# AJH_ss12144_v1_03.net
KiCad netlist of a schematic drawn in EAGLE
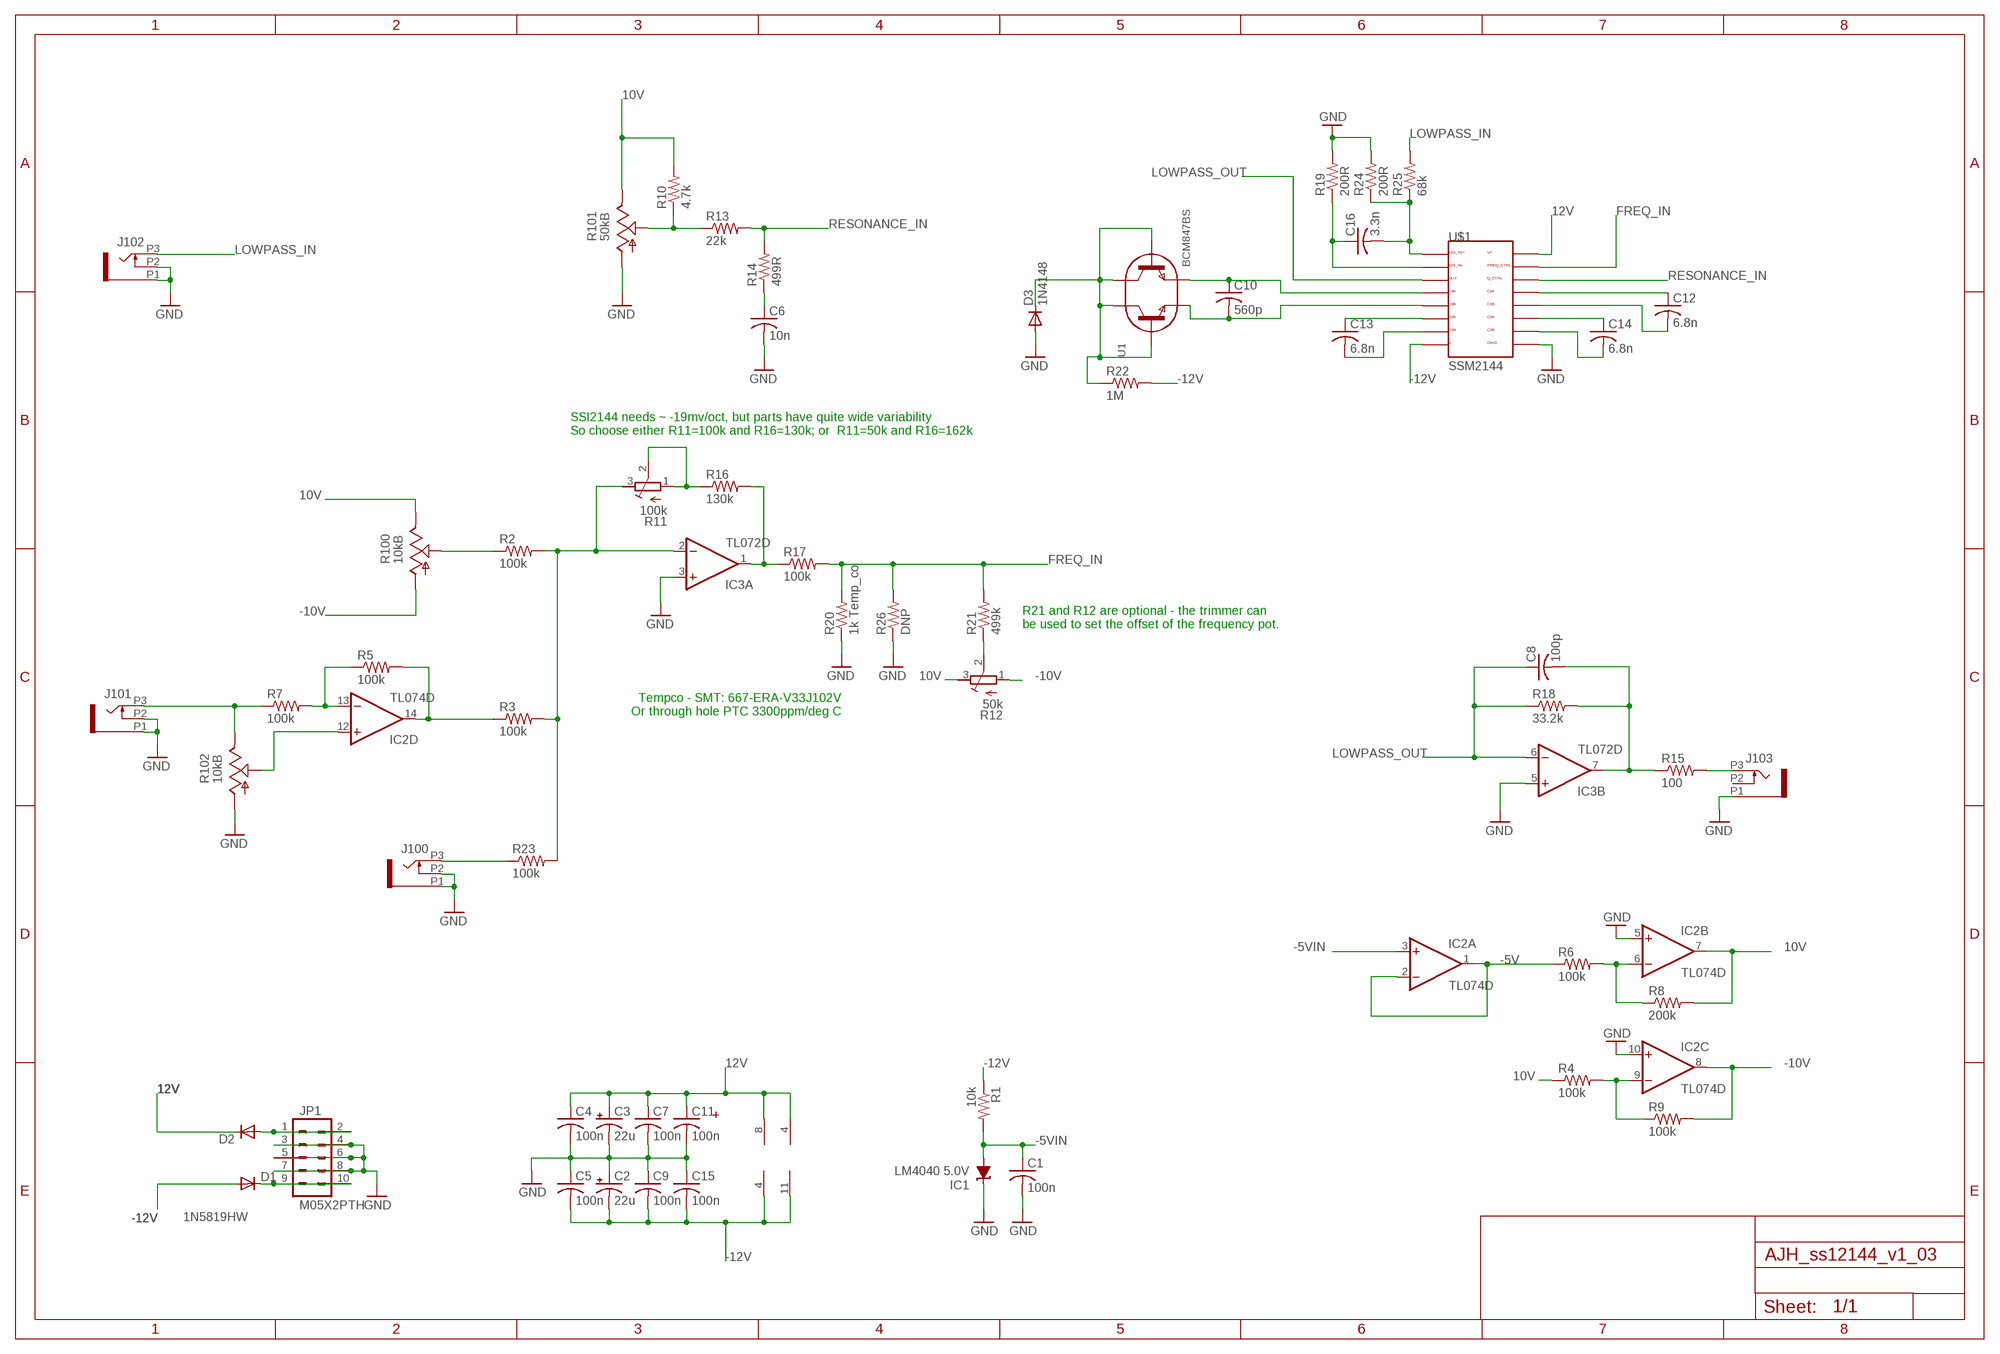
[diagram p0: schematic, sheet 1]

(export (version "E")
  (design (tool "Eeschema 10.0.6"))
  (components
    (comp (ref "C1")
      (value "100n")
      (footprint "eagle-import:C0603")
      (libsource (lib "eagle-import") (part "C-USC0603"))
    )
    (comp (ref "C2")
      (value "22u")
      (footprint "eagle-import:PANASONIC_B")
      (libsource (lib "eagle-import") (part "CPOL-USB"))
    )
    (comp (ref "C3")
      (value "22u")
      (footprint "eagle-import:PANASONIC_B")
      (libsource (lib "eagle-import") (part "CPOL-USB"))
    )
    (comp (ref "C4")
      (value "100n")
      (footprint "eagle-import:C0603")
      (libsource (lib "eagle-import") (part "C-USC0603"))
    )
    (comp (ref "C5")
      (value "100n")
      (footprint "eagle-import:C0603")
      (libsource (lib "eagle-import") (part "C-USC0603"))
    )
    (comp (ref "C6")
      (value "10n")
      (footprint "eagle-import:C0603")
      (libsource (lib "eagle-import") (part "C-USC0603"))
    )
    (comp (ref "C7")
      (value "100n")
      (footprint "eagle-import:C0603")
      (libsource (lib "eagle-import") (part "C-USC0603"))
    )
    (comp (ref "C8")
      (value "100p")
      (footprint "eagle-import:C0603")
      (libsource (lib "eagle-import") (part "C-USC0603"))
    )
    (comp (ref "C9")
      (value "100n")
      (footprint "eagle-import:C0603")
      (libsource (lib "eagle-import") (part "C-USC0603"))
    )
    (comp (ref "C10")
      (value "560p")
      (footprint "eagle-import:C0603")
      (libsource (lib "eagle-import") (part "C-USC0603"))
    )
    (comp (ref "C11")
      (value "100n")
      (footprint "eagle-import:C0603")
      (libsource (lib "eagle-import") (part "C-USC0603"))
    )
    (comp (ref "C12")
      (value "6.8n")
      (footprint "eagle-import:C0603")
      (libsource (lib "eagle-import") (part "C-USC0603"))
    )
    (comp (ref "C13")
      (value "6.8n")
      (footprint "eagle-import:C0603")
      (libsource (lib "eagle-import") (part "C-USC0603"))
    )
    (comp (ref "C14")
      (value "6.8n")
      (footprint "eagle-import:C0603")
      (libsource (lib "eagle-import") (part "C-USC0603"))
    )
    (comp (ref "C15")
      (value "100n")
      (footprint "eagle-import:C0603")
      (libsource (lib "eagle-import") (part "C-USC0603"))
    )
    (comp (ref "C16")
      (value "3.3n")
      (footprint "eagle-import:C0603")
      (libsource (lib "eagle-import") (part "C-USC0603"))
    )
    (comp (ref "D1")
      (value "1N5819HW")
      (footprint "eagle-import:SOD123")
      (libsource (lib "eagle-import") (part "DIODE-SOD123"))
    )
    (comp (ref "D2")
      (value "1N5819HW")
      (footprint "eagle-import:SOD123")
      (libsource (lib "eagle-import") (part "DIODE-SOD123"))
    )
    (comp (ref "D3")
      (value "1N4148")
      (footprint "eagle-import:SOD523")
      (libsource (lib "eagle-import") (part "DIODE-SOD523"))
    )
    (comp (ref "IC1")
      (value "LM4040 5.0V")
      (footprint "eagle-import:DBZ_R-PDSO-G3")
      (libsource (lib "eagle-import") (part "LM4041DBZC12"))
    )
    (comp (ref "IC2")
      (value "TL074D")
      (footprint "eagle-import:SO14")
      (libsource (lib "eagle-import") (part "TL074D"))
    )
    (comp (ref "IC3")
      (value "TL072D")
      (footprint "eagle-import:SO08")
      (libsource (lib "eagle-import") (part "TL072D"))
    )
    (comp (ref "J100")
      (value "PJ301_THONKICONN6")
      (footprint "eagle-import:WQP_PJ_301M6")
      (libsource (lib "eagle-import") (part "PJ301_THONKICONN6"))
    )
    (comp (ref "J101")
      (value "PJ301_THONKICONN6")
      (footprint "eagle-import:WQP_PJ_301M6")
      (libsource (lib "eagle-import") (part "PJ301_THONKICONN6"))
    )
    (comp (ref "J102")
      (value "PJ301_THONKICONN6")
      (footprint "eagle-import:WQP_PJ_301M6")
      (libsource (lib "eagle-import") (part "PJ301_THONKICONN6"))
    )
    (comp (ref "J103")
      (value "PJ301_THONKICONN6")
      (footprint "eagle-import:WQP_PJ_301M6")
      (libsource (lib "eagle-import") (part "PJ301_THONKICONN6"))
    )
    (comp (ref "JP1")
      (value "M05X2PTH")
      (footprint "eagle-import:AVR_ICSP")
      (libsource (lib "eagle-import") (part "M05X2PTH"))
    )
    (comp (ref "R1")
      (value "10k")
      (footprint "eagle-import:R0603")
      (libsource (lib "eagle-import") (part "resistor_R-US_R0603"))
    )
    (comp (ref "R2")
      (value "100k")
      (footprint "eagle-import:R0603")
      (libsource (lib "eagle-import") (part "resistor_R-US_R0603"))
    )
    (comp (ref "R3")
      (value "100k")
      (footprint "eagle-import:R0603")
      (libsource (lib "eagle-import") (part "resistor_R-US_R0603"))
    )
    (comp (ref "R4")
      (value "100k")
      (footprint "eagle-import:R0603")
      (libsource (lib "eagle-import") (part "resistor_R-US_R0603"))
    )
    (comp (ref "R5")
      (value "100k")
      (footprint "eagle-import:R0603")
      (libsource (lib "eagle-import") (part "resistor_R-US_R0603"))
    )
    (comp (ref "R6")
      (value "100k")
      (footprint "eagle-import:R0603")
      (libsource (lib "eagle-import") (part "resistor_R-US_R0603"))
    )
    (comp (ref "R7")
      (value "100k")
      (footprint "eagle-import:R0603")
      (libsource (lib "eagle-import") (part "resistor_R-US_R0603"))
    )
    (comp (ref "R8")
      (value "200k")
      (footprint "eagle-import:R0603")
      (libsource (lib "eagle-import") (part "resistor_R-US_R0603"))
    )
    (comp (ref "R9")
      (value "100k")
      (footprint "eagle-import:R0603")
      (libsource (lib "eagle-import") (part "resistor_R-US_R0603"))
    )
    (comp (ref "R10")
      (value "4.7k")
      (footprint "eagle-import:R0603")
      (libsource (lib "eagle-import") (part "resistor_R-US_R0603"))
    )
    (comp (ref "R11")
      (value "100k")
      (footprint "eagle-import:RTRIM3296X")
      (libsource (lib "eagle-import") (part "R-TRIMM3296X"))
    )
    (comp (ref "R12")
      (value "50k")
      (footprint "eagle-import:RTRIM3296X")
      (libsource (lib "eagle-import") (part "R-TRIMM3296X"))
    )
    (comp (ref "R13")
      (value "22k")
      (footprint "eagle-import:R0603")
      (libsource (lib "eagle-import") (part "resistor_R-US_R0603"))
    )
    (comp (ref "R14")
      (value "499R")
      (footprint "eagle-import:R0603")
      (libsource (lib "eagle-import") (part "resistor_R-US_R0603"))
    )
    (comp (ref "R15")
      (value "100")
      (footprint "eagle-import:R0603")
      (libsource (lib "eagle-import") (part "resistor_R-US_R0603"))
    )
    (comp (ref "R16")
      (value "130k")
      (footprint "eagle-import:R0603")
      (libsource (lib "eagle-import") (part "resistor_R-US_R0603"))
    )
    (comp (ref "R17")
      (value "100k")
      (footprint "eagle-import:R0603")
      (libsource (lib "eagle-import") (part "resistor_R-US_R0603"))
    )
    (comp (ref "R18")
      (value "33.2k")
      (footprint "eagle-import:R0603")
      (libsource (lib "eagle-import") (part "resistor_R-US_R0603"))
    )
    (comp (ref "R19")
      (value "200R")
      (footprint "eagle-import:R0603")
      (libsource (lib "eagle-import") (part "resistor_R-US_R0603"))
    )
    (comp (ref "R20")
      (value "1k Temp_co")
      (footprint "eagle-import:R0603")
      (libsource (lib "eagle-import") (part "resistor_R-US_R0603"))
    )
    (comp (ref "R21")
      (value "499k")
      (footprint "eagle-import:R0603")
      (libsource (lib "eagle-import") (part "resistor_R-US_R0603"))
    )
    (comp (ref "R22")
      (value "1M")
      (footprint "eagle-import:R0603")
      (libsource (lib "eagle-import") (part "resistor_R-US_R0603"))
    )
    (comp (ref "R23")
      (value "100k")
      (footprint "eagle-import:R0603")
      (libsource (lib "eagle-import") (part "resistor_R-US_R0603"))
    )
    (comp (ref "R24")
      (value "200R")
      (footprint "eagle-import:R0603")
      (libsource (lib "eagle-import") (part "resistor_R-US_R0603"))
    )
    (comp (ref "R25")
      (value "68k")
      (footprint "eagle-import:R0603")
      (libsource (lib "eagle-import") (part "resistor_R-US_R0603"))
    )
    (comp (ref "R26")
      (value "DNP")
      (footprint "eagle-import:0204_7")
      (libsource (lib "eagle-import") (part "R-US_0204/7"))
    )
    (comp (ref "R100")
      (value "10kB")
      (footprint "eagle-import:ALPS_POT_VERTICAL")
      (libsource (lib "eagle-import") (part "POT_USVERTICAL"))
    )
    (comp (ref "R101")
      (value "50kB")
      (footprint "eagle-import:ALPS_POT_VERTICAL")
      (libsource (lib "eagle-import") (part "POT_USVERTICAL"))
    )
    (comp (ref "R102")
      (value "10kB")
      (footprint "eagle-import:ALPS_POT_VERTICAL")
      (libsource (lib "eagle-import") (part "POT_USVERTICAL"))
    )
    (comp (ref "U$1")
      (value "SSM2144")
      (footprint "eagle-import:SSOP16")
      (libsource (lib "eagle-import") (part "SSM2144"))
    )
    (comp (ref "U1")
      (value "BCM847BS")
      (footprint "eagle-import:SOT363")
      (libsource (lib "eagle-import") (part "BCM847BS"))
    )
  )
  (nets
    (net (code "1") (name "/-5V") (class "Default")
      (node (ref "IC2") (pin "1") (pinfunction "OUT_1") (pintype "output"))
      (node (ref "IC2") (pin "2") (pinfunction "-IN_2") (pintype "input"))
      (node (ref "R6") (pin "1") (pinfunction "1_1") (pintype "passive"))
    )
    (net (code "2") (name "/-5VIN") (class "Default")
      (node (ref "C1") (pin "1") (pinfunction "1_1") (pintype "passive"))
      (node (ref "IC1") (pin "2") (pinfunction "A_2") (pintype "passive"))
      (node (ref "IC2") (pin "3") (pinfunction "+IN_3") (pintype "input"))
      (node (ref "R1") (pin "2") (pinfunction "2_2") (pintype "passive"))
    )
    (net (code "3") (name "/-10V") (class "Default")
      (node (ref "IC2") (pin "8") (pinfunction "OUT_8") (pintype "output"))
      (node (ref "R100") (pin "P$3") (pinfunction "A_P$3") (pintype "passive"))
      (node (ref "R12") (pin "1") (pinfunction "E_1") (pintype "passive"))
      (node (ref "R9") (pin "2") (pinfunction "2_2") (pintype "passive"))
    )
    (net (code "4") (name "/-12V") (class "Default")
      (node (ref "C15") (pin "2") (pinfunction "2_2") (pintype "passive"))
      (node (ref "C2") (pin "-") (pinfunction "-_-") (pintype "passive"))
      (node (ref "C5") (pin "2") (pinfunction "2_2") (pintype "passive"))
      (node (ref "C9") (pin "2") (pinfunction "2_2") (pintype "passive"))
      (node (ref "D1") (pin "A") (pinfunction "A_A") (pintype "passive"))
      (node (ref "IC2") (pin "11") (pinfunction "V-_11") (pintype "power_in"))
      (node (ref "IC3") (pin "4") (pinfunction "V-_4") (pintype "power_in"))
      (node (ref "R1") (pin "1") (pinfunction "1_1") (pintype "passive"))
      (node (ref "R22") (pin "2") (pinfunction "2_2") (pintype "passive"))
      (node (ref "U$1") (pin "8") (pinfunction "V-_8") (pintype "bidirectional"))
    )
    (net (code "5") (name "/10V") (class "Default")
      (node (ref "IC2") (pin "7") (pinfunction "OUT_7") (pintype "output"))
      (node (ref "R10") (pin "2") (pinfunction "2_2") (pintype "passive"))
      (node (ref "R100") (pin "P$1") (pinfunction "E_P$1") (pintype "passive"))
      (node (ref "R101") (pin "P$1") (pinfunction "E_P$1") (pintype "passive"))
      (node (ref "R12") (pin "3") (pinfunction "A_3") (pintype "passive"))
      (node (ref "R4") (pin "1") (pinfunction "1_1") (pintype "passive"))
      (node (ref "R8") (pin "2") (pinfunction "2_2") (pintype "passive"))
    )
    (net (code "6") (name "/12V") (class "Default")
      (node (ref "C11") (pin "1") (pinfunction "1_1") (pintype "passive"))
      (node (ref "C3") (pin "+") (pinfunction "+_+") (pintype "passive"))
      (node (ref "C4") (pin "1") (pinfunction "1_1") (pintype "passive"))
      (node (ref "C7") (pin "1") (pinfunction "1_1") (pintype "passive"))
      (node (ref "D2") (pin "C") (pinfunction "C_C") (pintype "passive"))
      (node (ref "IC2") (pin "4") (pinfunction "V+_4") (pintype "power_in"))
      (node (ref "IC3") (pin "8") (pinfunction "V+_8") (pintype "power_in"))
      (node (ref "U$1") (pin "16") (pinfunction "V+_16") (pintype "bidirectional"))
    )
    (net (code "7") (name "/FREQ_IN") (class "Default")
      (node (ref "R17") (pin "2") (pinfunction "2_2") (pintype "passive"))
      (node (ref "R20") (pin "2") (pinfunction "2_2") (pintype "passive"))
      (node (ref "R21") (pin "2") (pinfunction "2_2") (pintype "passive"))
      (node (ref "R26") (pin "2") (pinfunction "2_2") (pintype "passive"))
      (node (ref "U$1") (pin "15") (pinfunction "FREQ_CTRL_15") (pintype "bidirectional"))
    )
    (net (code "8") (name "/LOWPASS_IN") (class "Default")
      (node (ref "J102") (pin "P3") (pinfunction "3_P3") (pintype "passive"))
      (node (ref "R25") (pin "2") (pinfunction "2_2") (pintype "passive"))
    )
    (net (code "9") (name "/LOWPASS_OUT") (class "Default")
      (node (ref "C8") (pin "1") (pinfunction "1_1") (pintype "passive"))
      (node (ref "IC3") (pin "6") (pinfunction "-IN_6") (pintype "input"))
      (node (ref "R18") (pin "1") (pinfunction "1_1") (pintype "passive"))
      (node (ref "U$1") (pin "3") (pinfunction "OUT_3") (pintype "bidirectional"))
    )
    (net (code "10") (name "/RESONANCE_IN") (class "Default")
      (node (ref "R13") (pin "2") (pinfunction "2_2") (pintype "passive"))
      (node (ref "R14") (pin "2") (pinfunction "2_2") (pintype "passive"))
      (node (ref "U$1") (pin "14") (pinfunction "Q_CTRL_14") (pintype "bidirectional"))
    )
    (net (code "11") (name "GND") (class "Default")
      (node (ref "C1") (pin "2") (pinfunction "2_2") (pintype "passive"))
      (node (ref "C11") (pin "2") (pinfunction "2_2") (pintype "passive"))
      (node (ref "C15") (pin "1") (pinfunction "1_1") (pintype "passive"))
      (node (ref "C2") (pin "+") (pinfunction "+_+") (pintype "passive"))
      (node (ref "C3") (pin "-") (pinfunction "-_-") (pintype "passive"))
      (node (ref "C4") (pin "2") (pinfunction "2_2") (pintype "passive"))
      (node (ref "C5") (pin "1") (pinfunction "1_1") (pintype "passive"))
      (node (ref "C6") (pin "2") (pinfunction "2_2") (pintype "passive"))
      (node (ref "C7") (pin "2") (pinfunction "2_2") (pintype "passive"))
      (node (ref "C9") (pin "1") (pinfunction "1_1") (pintype "passive"))
      (node (ref "D3") (pin "A") (pinfunction "A_A") (pintype "passive"))
      (node (ref "IC1") (pin "1") (pinfunction "C_1") (pintype "passive"))
      (node (ref "IC2") (pin "10") (pinfunction "+IN_10") (pintype "input"))
      (node (ref "IC2") (pin "5") (pinfunction "+IN_5") (pintype "input"))
      (node (ref "IC3") (pin "3") (pinfunction "+IN_3") (pintype "input"))
      (node (ref "IC3") (pin "5") (pinfunction "+IN_5") (pintype "input"))
      (node (ref "J100") (pin "P1") (pinfunction "1_P1") (pintype "passive"))
      (node (ref "J100") (pin "P2") (pinfunction "2_P2") (pintype "passive"))
      (node (ref "J101") (pin "P1") (pinfunction "1_P1") (pintype "passive"))
      (node (ref "J101") (pin "P2") (pinfunction "2_P2") (pintype "passive"))
      (node (ref "J102") (pin "P1") (pinfunction "1_P1") (pintype "passive"))
      (node (ref "J102") (pin "P2") (pinfunction "2_P2") (pintype "passive"))
      (node (ref "J103") (pin "P1") (pinfunction "1_P1") (pintype "passive"))
      (node (ref "JP1") (pin "3") (pinfunction "3_3") (pintype "passive"))
      (node (ref "JP1") (pin "4") (pinfunction "4_4") (pintype "passive"))
      (node (ref "JP1") (pin "5") (pinfunction "5_5") (pintype "passive"))
      (node (ref "JP1") (pin "6") (pinfunction "6_6") (pintype "passive"))
      (node (ref "JP1") (pin "7") (pinfunction "7_7") (pintype "passive"))
      (node (ref "JP1") (pin "8") (pinfunction "8_8") (pintype "passive"))
      (node (ref "R101") (pin "P$3") (pinfunction "A_P$3") (pintype "passive"))
      (node (ref "R102") (pin "P$3") (pinfunction "A_P$3") (pintype "passive"))
      (node (ref "R19") (pin "2") (pinfunction "2_2") (pintype "passive"))
      (node (ref "R20") (pin "1") (pinfunction "1_1") (pintype "passive"))
      (node (ref "R24") (pin "2") (pinfunction "2_2") (pintype "passive"))
      (node (ref "R26") (pin "1") (pinfunction "1_1") (pintype "passive"))
      (node (ref "U$1") (pin "9") (pinfunction "GND_9") (pintype "bidirectional"))
    )
    (net (code "12") (name "Net-(C6-Pad1)") (class "Default")
      (node (ref "C6") (pin "1") (pinfunction "1_1") (pintype "passive"))
      (node (ref "R14") (pin "1") (pinfunction "1_1") (pintype "passive"))
    )
    (net (code "13") (name "Net-(D1-PadC)") (class "Default")
      (node (ref "D1") (pin "C") (pinfunction "C_C") (pintype "passive"))
      (node (ref "JP1") (pin "10") (pinfunction "10_10") (pintype "passive"))
      (node (ref "JP1") (pin "9") (pinfunction "9_9") (pintype "passive"))
    )
    (net (code "14") (name "Net-(D2-PadA)") (class "Default")
      (node (ref "D2") (pin "A") (pinfunction "A_A") (pintype "passive"))
      (node (ref "JP1") (pin "1") (pinfunction "1_1") (pintype "passive"))
      (node (ref "JP1") (pin "2") (pinfunction "2_2") (pintype "passive"))
    )
    (net (code "15") (name "Net-(IC2B--IN)") (class "Default")
      (node (ref "IC2") (pin "6") (pinfunction "-IN_6") (pintype "input"))
      (node (ref "R6") (pin "2") (pinfunction "2_2") (pintype "passive"))
      (node (ref "R8") (pin "1") (pinfunction "1_1") (pintype "passive"))
    )
    (net (code "16") (name "Net-(IC2C--IN)") (class "Default")
      (node (ref "IC2") (pin "9") (pinfunction "-IN_9") (pintype "input"))
      (node (ref "R4") (pin "2") (pinfunction "2_2") (pintype "passive"))
      (node (ref "R9") (pin "1") (pinfunction "1_1") (pintype "passive"))
    )
    (net (code "17") (name "Net-(IC2D-+IN)") (class "Default")
      (node (ref "IC2") (pin "12") (pinfunction "+IN_12") (pintype "input"))
      (node (ref "R102") (pin "P$2") (pinfunction "S_P$2") (pintype "passive"))
    )
    (net (code "18") (name "Net-(IC2D--IN)") (class "Default")
      (node (ref "IC2") (pin "13") (pinfunction "-IN_13") (pintype "input"))
      (node (ref "R5") (pin "1") (pinfunction "1_1") (pintype "passive"))
      (node (ref "R7") (pin "2") (pinfunction "2_2") (pintype "passive"))
    )
    (net (code "19") (name "Net-(IC2D-OUT)") (class "Default")
      (node (ref "IC2") (pin "14") (pinfunction "OUT_14") (pintype "output"))
      (node (ref "R3") (pin "1") (pinfunction "1_1") (pintype "passive"))
      (node (ref "R5") (pin "2") (pinfunction "2_2") (pintype "passive"))
    )
    (net (code "20") (name "Net-(IC3A--IN)") (class "Default")
      (node (ref "IC3") (pin "2") (pinfunction "-IN_2") (pintype "input"))
      (node (ref "R11") (pin "3") (pinfunction "A_3") (pintype "passive"))
      (node (ref "R2") (pin "2") (pinfunction "2_2") (pintype "passive"))
      (node (ref "R23") (pin "2") (pinfunction "2_2") (pintype "passive"))
      (node (ref "R3") (pin "2") (pinfunction "2_2") (pintype "passive"))
    )
    (net (code "21") (name "Net-(IC3A-OUT)") (class "Default")
      (node (ref "IC3") (pin "1") (pinfunction "OUT_1") (pintype "output"))
      (node (ref "R16") (pin "2") (pinfunction "2_2") (pintype "passive"))
      (node (ref "R17") (pin "1") (pinfunction "1_1") (pintype "passive"))
    )
    (net (code "22") (name "Net-(IC3B-OUT)") (class "Default")
      (node (ref "C8") (pin "2") (pinfunction "2_2") (pintype "passive"))
      (node (ref "IC3") (pin "7") (pinfunction "OUT_7") (pintype "output"))
      (node (ref "R15") (pin "1") (pinfunction "1_1") (pintype "passive"))
      (node (ref "R18") (pin "2") (pinfunction "2_2") (pintype "passive"))
    )
    (net (code "23") (name "Net-(J100-3)") (class "Default")
      (node (ref "J100") (pin "P3") (pinfunction "3_P3") (pintype "passive"))
      (node (ref "R23") (pin "1") (pinfunction "1_1") (pintype "passive"))
    )
    (net (code "24") (name "Net-(J101-3)") (class "Default")
      (node (ref "J101") (pin "P3") (pinfunction "3_P3") (pintype "passive"))
      (node (ref "R102") (pin "P$1") (pinfunction "E_P$1") (pintype "passive"))
      (node (ref "R7") (pin "1") (pinfunction "1_1") (pintype "passive"))
    )
    (net (code "25") (name "Net-(J103-3)") (class "Default")
      (node (ref "J103") (pin "P3") (pinfunction "3_P3") (pintype "passive"))
      (node (ref "R15") (pin "2") (pinfunction "2_2") (pintype "passive"))
    )
    (net (code "26") (name "Net-(R11-E)") (class "Default")
      (node (ref "R11") (pin "1") (pinfunction "E_1") (pintype "passive"))
      (node (ref "R11") (pin "2") (pinfunction "S_2") (pintype "passive"))
      (node (ref "R16") (pin "1") (pinfunction "1_1") (pintype "passive"))
    )
    (net (code "27") (name "Net-(R12-S)") (class "Default")
      (node (ref "R12") (pin "2") (pinfunction "S_2") (pintype "passive"))
      (node (ref "R21") (pin "1") (pinfunction "1_1") (pintype "passive"))
    )
    (net (code "28") (name "Net-(R100-S)") (class "Default")
      (node (ref "R100") (pin "P$2") (pinfunction "S_P$2") (pintype "passive"))
      (node (ref "R2") (pin "1") (pinfunction "1_1") (pintype "passive"))
    )
    (net (code "29") (name "Net-(R101-S)") (class "Default")
      (node (ref "R10") (pin "1") (pinfunction "1_1") (pintype "passive"))
      (node (ref "R101") (pin "P$2") (pinfunction "S_P$2") (pintype "passive"))
      (node (ref "R13") (pin "1") (pinfunction "1_1") (pintype "passive"))
    )
    (net (code "30") (name "Net-(U$1-C1A)") (class "Default")
      (node (ref "C12") (pin "1") (pinfunction "1_1") (pintype "passive"))
      (node (ref "U$1") (pin "13") (pinfunction "C1A_13") (pintype "bidirectional"))
    )
    (net (code "31") (name "Net-(U$1-C1B)") (class "Default")
      (node (ref "C12") (pin "2") (pinfunction "2_2") (pintype "passive"))
      (node (ref "U$1") (pin "12") (pinfunction "C1B_12") (pintype "bidirectional"))
    )
    (net (code "32") (name "Net-(U$1-C2A)") (class "Default")
      (node (ref "C14") (pin "1") (pinfunction "1_1") (pintype "passive"))
      (node (ref "U$1") (pin "11") (pinfunction "C2A_11") (pintype "bidirectional"))
    )
    (net (code "33") (name "Net-(U$1-C2B)") (class "Default")
      (node (ref "C14") (pin "2") (pinfunction "2_2") (pintype "passive"))
      (node (ref "U$1") (pin "10") (pinfunction "C2B_10") (pintype "bidirectional"))
    )
    (net (code "34") (name "Net-(U$1-C3A)") (class "Default")
      (node (ref "C13") (pin "1") (pinfunction "1_1") (pintype "passive"))
      (node (ref "U$1") (pin "6") (pinfunction "C3A_6") (pintype "bidirectional"))
    )
    (net (code "35") (name "Net-(U$1-C3B)") (class "Default")
      (node (ref "C13") (pin "2") (pinfunction "2_2") (pintype "passive"))
      (node (ref "U$1") (pin "7") (pinfunction "C3B_7") (pintype "bidirectional"))
    )
    (net (code "36") (name "Net-(U$1-C4A)") (class "Default")
      (node (ref "C10") (pin "1") (pinfunction "1_1") (pintype "passive"))
      (node (ref "U$1") (pin "4") (pinfunction "C4A_4") (pintype "bidirectional"))
      (node (ref "U1") (pin "4") (pinfunction "E2_4") (pintype "passive"))
    )
    (net (code "37") (name "Net-(U$1-C4B)") (class "Default")
      (node (ref "C10") (pin "2") (pinfunction "2_2") (pintype "passive"))
      (node (ref "U$1") (pin "5") (pinfunction "C4B_5") (pintype "bidirectional"))
      (node (ref "U1") (pin "1") (pinfunction "E1_1") (pintype "passive"))
    )
    (net (code "38") (name "Net-(U$1-SIG_IN+)") (class "Default")
      (node (ref "C16") (pin "2") (pinfunction "2_2") (pintype "passive"))
      (node (ref "R24") (pin "1") (pinfunction "1_1") (pintype "passive"))
      (node (ref "R25") (pin "1") (pinfunction "1_1") (pintype "passive"))
      (node (ref "U$1") (pin "1") (pinfunction "SIG_IN+_1") (pintype "bidirectional"))
    )
    (net (code "39") (name "Net-(U$1-SIG_IN-)") (class "Default")
      (node (ref "C16") (pin "1") (pinfunction "1_1") (pintype "passive"))
      (node (ref "R19") (pin "1") (pinfunction "1_1") (pintype "passive"))
      (node (ref "U$1") (pin "2") (pinfunction "SIG_IN-_2") (pintype "bidirectional"))
    )
    (net (code "40") (name "Net-(U1-B1)") (class "Default")
      (node (ref "D3") (pin "C") (pinfunction "C_C") (pintype "passive"))
      (node (ref "R22") (pin "1") (pinfunction "1_1") (pintype "passive"))
      (node (ref "U1") (pin "2") (pinfunction "B1_2") (pintype "passive"))
      (node (ref "U1") (pin "3") (pinfunction "C2_3") (pintype "passive"))
      (node (ref "U1") (pin "5") (pinfunction "B2_5") (pintype "passive"))
      (node (ref "U1") (pin "6") (pinfunction "C1_6") (pintype "passive"))
    )
    (net (code "41") (name "unconnected-(J103-2-PadP2)") (class "Default")
      (node (ref "J103") (pin "P2") (pinfunction "2_P2") (pintype "passive"))
    )
  )
)
